# schematic.net
KiCad netlist of a schematic drawn in Altium Designer
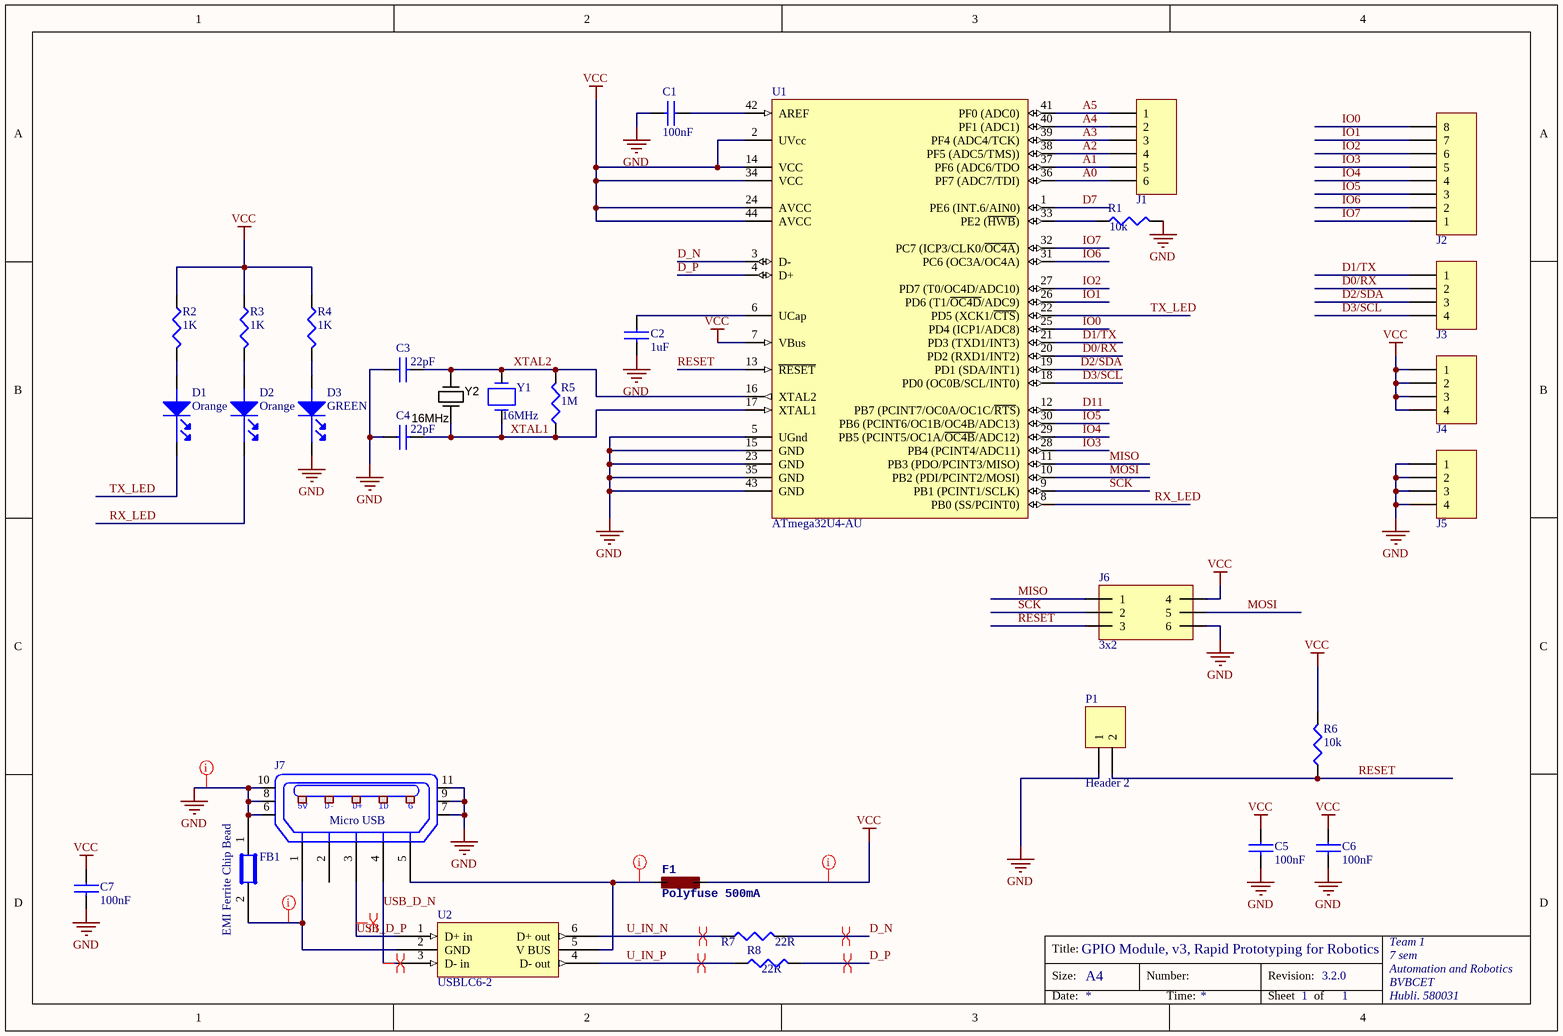
[diagram p0: schematic.SchDoc]

(export (version "E")
  (design (tool "Eeschema 10.0.6"))
  (components
    (comp (ref "C1")
      (value "100nF")
      (footprint "C0805")
      (description "CAP CER 16V 20% X5R 0805")
      (fields
        (field (name "MANUFACTURER") "TDK Corporation")
        (field (name "MANUFACTURER PART NUMBER") "C2012X5R1C106M/1.25")
      )
      (libsource (lib "GPIO_Module") (part "C2012X5R1C106M"))
    )
    (comp (ref "C2")
      (value "1uF")
      (footprint "C0805")
      (description "CAP CER 16V 20% X5R 0805")
      (fields
        (field (name "MANUFACTURER") "TDK Corporation")
        (field (name "MANUFACTURER PART NUMBER") "C2012X5R1C106M/1.25")
      )
      (libsource (lib "GPIO_Module") (part "C2012X5R1C106M"))
    )
    (comp (ref "C3")
      (value "22pF")
      (footprint "C0805")
      (description "CAP CER 22pF 50V 5% NP0 0805")
      (fields
        (field (name "MANUFACTURER") "Kemet")
        (field (name "MANUFACTURER PART NUMBER") "C0805C180J5GACTU")
        (field (name ".CREATOR") "MM")
        (field (name ".CHECKED PCB") "RF")
        (field (name ".CHECKED SCH") "RF")
      )
      (libsource (lib "GPIO_Module") (part "C0805C180J5GACTU"))
    )
    (comp (ref "C4")
      (value "22pF")
      (footprint "C0805")
      (description "CAP CER 22pF 50V 5% NP0 0805")
      (fields
        (field (name "MANUFACTURER") "Kemet")
        (field (name "MANUFACTURER PART NUMBER") "C0805C180J5GACTU")
        (field (name ".CREATOR") "MM")
        (field (name ".CHECKED PCB") "RF")
        (field (name ".CHECKED SCH") "RF")
      )
      (libsource (lib "GPIO_Module") (part "C0805C180J5GACTU"))
    )
    (comp (ref "C5")
      (value "100nF")
      (footprint "C0805")
      (description "CAP CER 0.1UF 50V 10% X7R 0805")
      (fields
        (field (name "MANUFACTURER") "TDK Corporation")
        (field (name "MANUFACTURER PART NUMBER") "C2012X7R1H104K085AA")
        (field (name ".CREATOR") "MM")
        (field (name ".CHECKED PCB") "RF")
        (field (name ".CHECKED SCH") "RF")
      )
      (libsource (lib "GPIO_Module") (part "C2012X7R1H104K085AA"))
    )
    (comp (ref "C6")
      (value "100nF")
      (footprint "C0805")
      (description "CAP CER 0.1UF 50V 10% X7R 0805")
      (fields
        (field (name "MANUFACTURER") "TDK Corporation")
        (field (name "MANUFACTURER PART NUMBER") "C2012X7R1H104K085AA")
        (field (name ".CREATOR") "MM")
        (field (name ".CHECKED PCB") "RF")
        (field (name ".CHECKED SCH") "RF")
      )
      (libsource (lib "GPIO_Module") (part "C2012X7R1H104K085AA"))
    )
    (comp (ref "C7")
      (value "100nF")
      (footprint "C0805")
      (description "CAP CER 0.1UF 50V 10% X7R 0805")
      (fields
        (field (name "MANUFACTURER") "TDK Corporation")
        (field (name "MANUFACTURER PART NUMBER") "C2012X7R1H104K085AA")
        (field (name ".CREATOR") "MM")
        (field (name ".CHECKED PCB") "RF")
        (field (name ".CHECKED SCH") "RF")
      )
      (libsource (lib "GPIO_Module") (part "C2012X7R1H104K085AA"))
    )
    (comp (ref "D1")
      (value "Orange")
      (footprint "LED_0603")
      (description "LED SMARTLED ORANGE 606NM 0603")
      (fields
        (field (name "MANUFACTURER") "OSRAM Opto Semiconductors Inc")
        (field (name "MANUFACTURER PART NUMBER") "LO L29K-H2K1-24-Z")
      )
      (libsource (lib "GPIO_Module") (part "LO L29K-H2K1-24-Z"))
    )
    (comp (ref "D2")
      (value "Orange")
      (footprint "LED_0603")
      (description "LED SMARTLED ORANGE 606NM 0603")
      (fields
        (field (name "MANUFACTURER") "OSRAM Opto Semiconductors Inc")
        (field (name "MANUFACTURER PART NUMBER") "LO L29K-H2K1-24-Z")
      )
      (libsource (lib "GPIO_Module") (part "LO L29K-H2K1-24-Z"))
    )
    (comp (ref "D3")
      (value "GREEN")
      (footprint "LED_0603")
      (description "LED SMARTLED ORANGE 606NM 0603")
      (fields
        (field (name "MANUFACTURER") "OSRAM Opto Semiconductors Inc")
        (field (name "MANUFACTURER PART NUMBER") "LO L29K-H2K1-24-Z")
      )
      (libsource (lib "GPIO_Module") (part "LO L29K-H2K1-24-Z"))
    )
    (comp (ref "F1")
      (value "Polyfuse 500mA")
      (footprint "L1812")
      (libsource (lib "GPIO_Module") (part "L-EUL1812"))
    )
    (comp (ref "FB1")
      (value "EMI Ferrite Chip Bead")
      (footprint "C0805")
      (description "Multilayer Ferrite Beads, Chip Beads in SMD 0805 package")
      (fields (field (name "MANUFACTURER") "Bourns") (field (name "MANUFACTURER PART NUMBER") "MH2029-300Y"))
      (libsource (lib "GPIO_Module") (part "MPZ2012S601AT000"))
    )
    (comp (ref "J1")
      (value "06p")
      (footprint "61300611821")
      (description "WR-PHD 2.54 mm Socket Header, 06p")
      (fields (field (name "PARTNUMBER") "61300611821") (field (name "PUBLISHER") "Wurth Elektronik"))
      (libsource (lib "ALTIUM-PHD_2_54_ANGLED_DUAL_SOCKET_HEADER_6130XX243121-rev16c") (part "61300611821"))
    )
    (comp (ref "J2")
      (value "08p")
      (footprint "61300811821")
      (description "WR-PHD 2.54 mm Socket Header, 08p")
      (fields (field (name "PARTNUMBER") "61300811821") (field (name "PUBLISHER") "Wurth Elektronik"))
      (libsource (lib "ALTIUM-PHD_2_54_ANGLED_DUAL_SOCKET_HEADER_6130XX243121-rev16c") (part "61300811821"))
    )
    (comp (ref "J3")
      (value "04p")
      (footprint "61300411821")
      (description "WR-PHD 2.54 mm Socket Header, 04p")
      (fields (field (name "PARTNUMBER") "61300411821") (field (name "PUBLISHER") "Wurth Elektronik"))
      (libsource (lib "ALTIUM-PHD_2_54_ANGLED_DUAL_SOCKET_HEADER_6130XX243121-rev16c") (part "61300411821"))
    )
    (comp (ref "J4")
      (value "04p")
      (footprint "61300411821")
      (description "WR-PHD 2.54 mm Socket Header, 04p")
      (fields (field (name "PARTNUMBER") "61300411821") (field (name "PUBLISHER") "Wurth Elektronik"))
      (libsource (lib "ALTIUM-PHD_2_54_ANGLED_DUAL_SOCKET_HEADER_6130XX243121-rev16c") (part "61300411821"))
    )
    (comp (ref "J5")
      (value "04p")
      (footprint "61300411821")
      (description "WR-PHD 2.54 mm Socket Header, 04p")
      (fields (field (name "PARTNUMBER") "61300411821") (field (name "PUBLISHER") "Wurth Elektronik"))
      (libsource (lib "ALTIUM-PHD_2_54_ANGLED_DUAL_SOCKET_HEADER_6130XX243121-rev16c") (part "61300411821"))
    )
    (comp (ref "J6")
      (value "3x2")
      (footprint "Headers:Male 3x2")
      (description "3x2 100mil Header")
      (libsource (lib "GPIO_Module") (part "3x2"))
    )
    (comp (ref "J7")
      (value "Micro USB")
      (footprint "10118193")
      (description "CONN USB MICRO B RECPT SMT R/A")
      (fields
        (field (name "MANUFACTURER") "FCI")
        (field (name "MANUFACTURER PART NUMBER") "10118193-0001LF")
        (field (name ".CREATOR") "MM")
        (field (name ".CHECKED PCB") "RF")
        (field (name ".CHECKED SCH") "MM")
      )
      (libsource (lib "GPIO_Module") (part "10118193-0001LF"))
    )
    (comp (ref "P1")
      (value "Header 2")
      (footprint "HDR1X2")
      (description "Header, 2-Pin")
      (fields (field (name "PUBLISHER") "Altium Limited"))
      (libsource (lib "Miscellaneous Connectors") (part "Header 2"))
    )
    (comp (ref "R1")
      (value "10k")
      (footprint "R0805")
      (description "RES SMD 10K OHM 1% 1/8W 0805")
      (fields
        (field (name "MANUFACTURER") "Yageo")
        (field (name "MANUFACTURER PART NUMBER") "RC0805FR-0710KL")
        (field (name ".CREATOR") "MM")
        (field (name ".CHECKED PCB") "RF")
        (field (name ".CHECKED SCH") "RF")
      )
      (libsource (lib "GPIO_Module") (part "RC0805FR-0710KL"))
    )
    (comp (ref "R2")
      (value "1K")
      (footprint "R0805")
      (description "RES SMD 1K OHM 1% 1/8W 0805")
      (fields
        (field (name "MANUFACTURER") "Yageo")
        (field (name "MANUFACTURER PART NUMBER") "RC0805FR-071KL")
        (field (name ".CREATOR") "MM")
        (field (name ".CHECKED PCB") "RF")
        (field (name ".CHECKED SCH") "RF")
      )
      (libsource (lib "GPIO_Module") (part "RC0805FR-071KL"))
    )
    (comp (ref "R3")
      (value "1K")
      (footprint "R0805")
      (description "RES SMD 1K OHM 1% 1/8W 0805")
      (fields
        (field (name "MANUFACTURER") "Yageo")
        (field (name "MANUFACTURER PART NUMBER") "RC0805FR-071KL")
        (field (name ".CREATOR") "MM")
        (field (name ".CHECKED PCB") "RF")
        (field (name ".CHECKED SCH") "RF")
      )
      (libsource (lib "GPIO_Module") (part "RC0805FR-071KL"))
    )
    (comp (ref "R4")
      (value "1K")
      (footprint "R0805")
      (description "RES SMD 1K OHM 1% 1/8W 0805")
      (fields
        (field (name "MANUFACTURER") "Yageo")
        (field (name "MANUFACTURER PART NUMBER") "RC0805FR-071KL")
        (field (name ".CREATOR") "MM")
        (field (name ".CHECKED PCB") "RF")
        (field (name ".CHECKED SCH") "RF")
      )
      (libsource (lib "GPIO_Module") (part "RC0805FR-071KL"))
    )
    (comp (ref "R5")
      (value "1M")
      (footprint "R0805")
      (description "RES SMD 1M OHM 1% 1/8W 0805")
      (fields
        (field (name "MANUFACTURER") "Yageo")
        (field (name "MANUFACTURER PART NUMBER") "RC0805FR-071ML")
        (field (name ".CREATOR") "MM")
        (field (name ".CHECKED PCB") "RF")
        (field (name ".CHECKED SCH") "RF")
      )
      (libsource (lib "GPIO_Module") (part "RC0805FR-071ML"))
    )
    (comp (ref "R6")
      (value "10k")
      (footprint "R0805")
      (description "RES SMD 10K OHM 1% 1/8W 0805")
      (fields
        (field (name "MANUFACTURER") "Yageo")
        (field (name "MANUFACTURER PART NUMBER") "RC0805FR-0710KL")
        (field (name ".CREATOR") "MM")
        (field (name ".CHECKED PCB") "RF")
        (field (name ".CHECKED SCH") "RF")
      )
      (libsource (lib "GPIO_Module") (part "RC0805FR-0710KL"))
    )
    (comp (ref "R7")
      (value "22R")
      (footprint "R0805")
      (description "RES SMD 22 OHM 1% 1/8W 0805")
      (fields
        (field (name "MANUFACTURER") "Yageo")
        (field (name "MANUFACTURER PART NUMBER") "RC0805FR-0722RL")
        (field (name ".CREATOR") "MM")
        (field (name ".CHECKED PCB") "RF")
        (field (name ".CHECKED SCH") "RF")
      )
      (libsource (lib "GPIO_Module") (part "RC0805FR-0722RL"))
    )
    (comp (ref "R8")
      (value "22R")
      (footprint "R0805")
      (description "RES SMD 22 OHM 1% 1/8W 0805")
      (fields
        (field (name "MANUFACTURER") "Yageo")
        (field (name "MANUFACTURER PART NUMBER") "RC0805FR-0722RL")
        (field (name ".CREATOR") "MM")
        (field (name ".CHECKED PCB") "RF")
        (field (name ".CHECKED SCH") "RF")
      )
      (libsource (lib "GPIO_Module") (part "RC0805FR-0722RL"))
    )
    (comp (ref "U1")
      (value "ATmega32U4-AU")
      (footprint "44ML_M")
      (fields (field (name "PUBLISHER") "Altium Limited"))
      (libsource (lib "GPIO_Module") (part "ATmega32U4-AU"))
    )
    (comp (ref "U2")
      (value "USBLC6-2")
      (footprint "TSOT23-6")
      (libsource (lib "GPIO_Module") (part "USBLC6-2"))
    )
    (comp (ref "Y1")
      (value "16MHz")
      (footprint "ABM7_v1_1_BIG")
      (description "CRYSTAL 16MHZ 18PF SMD")
      (fields
        (field (name "MANUFACTURER") "Abracon LLC")
        (field (name "MANUFACTURER PART NUMBER") "ABM7-16.000MHZ-D2Y-T")
        (field (name ".CREATOR") "MM")
        (field (name ".CHECKED PCB") "RF")
        (field (name ".CHECKED SCH") "RF")
      )
      (libsource (lib "GPIO_Module") (part "ABM7-16.000MHZ-D2Y-T"))
    )
    (comp (ref "Y2")
      (value "16MHz")
      (footprint "CRYSTAL_HC49-US-SM")
      (description "Resonator Ceramic 6.00 MHz 30ppm")
      (libsource (lib "PBL - Resonators") (part "Crystal_6MHz_HC49/US"))
    )
  )
  (nets
    (net (code "1") (name "/A0") (class "Default")
      (node (ref "J1") (pin "6") (pinfunction "6_6") (pintype "passive"))
      (node (ref "U1") (pin "36") (pinfunction "PF7_(ADC7/TDI)_36") (pintype "bidirectional"))
    )
    (net (code "2") (name "/A1") (class "Default")
      (node (ref "J1") (pin "5") (pinfunction "5_5") (pintype "passive"))
      (node (ref "U1") (pin "37") (pinfunction "PF6_(ADC6/TDO_37") (pintype "bidirectional"))
    )
    (net (code "3") (name "/A2") (class "Default")
      (node (ref "J1") (pin "4") (pinfunction "4_4") (pintype "passive"))
      (node (ref "U1") (pin "38") (pinfunction "PF5_(ADC5/TMS))_38") (pintype "bidirectional"))
    )
    (net (code "4") (name "/A3") (class "Default")
      (node (ref "J1") (pin "3") (pinfunction "3_3") (pintype "passive"))
      (node (ref "U1") (pin "39") (pinfunction "PF4_(ADC4/TCK)_39") (pintype "bidirectional"))
    )
    (net (code "5") (name "/A4") (class "Default")
      (node (ref "J1") (pin "2") (pinfunction "2_2") (pintype "passive"))
      (node (ref "U1") (pin "40") (pinfunction "PF1_(ADC1)_40") (pintype "bidirectional"))
    )
    (net (code "6") (name "/A5") (class "Default")
      (node (ref "J1") (pin "1") (pinfunction "1_1") (pintype "passive"))
      (node (ref "U1") (pin "41") (pinfunction "PF0_(ADC0)_41") (pintype "bidirectional"))
    )
    (net (code "7") (name "/D0{slash}RX") (class "Default")
      (node (ref "J3") (pin "2") (pinfunction "2_2") (pintype "passive"))
      (node (ref "U1") (pin "20") (pinfunction "PD2_(RXD1/INT2)_20") (pintype "bidirectional"))
    )
    (net (code "8") (name "/D1{slash}TX") (class "Default")
      (node (ref "J3") (pin "1") (pinfunction "1_1") (pintype "passive"))
      (node (ref "U1") (pin "21") (pinfunction "PD3_(TXD1/INT3)_21") (pintype "bidirectional"))
    )
    (net (code "9") (name "/D2{slash}SDA") (class "Default")
      (node (ref "J3") (pin "3") (pinfunction "3_3") (pintype "passive"))
      (node (ref "U1") (pin "19") (pinfunction "PD1_(SDA/INT1)_19") (pintype "bidirectional"))
    )
    (net (code "10") (name "/D3{slash}SCL") (class "Default")
      (node (ref "J3") (pin "4") (pinfunction "4_4") (pintype "passive"))
      (node (ref "U1") (pin "18") (pinfunction "PD0_(OC0B/SCL/INT0)_18") (pintype "bidirectional"))
    )
    (net (code "11") (name "/D7") (class "Default")
      (node (ref "U1") (pin "1") (pinfunction "PE6_(INT.6/AIN0)_1") (pintype "bidirectional"))
    )
    (net (code "12") (name "/D11") (class "Default")
      (node (ref "U1") (pin "12") (pinfunction "PB7_(PCINT7/OC0A/OC1C/~{RTS})_12") (pintype "bidirectional"))
    )
    (net (code "13") (name "/D_N") (class "Default")
      (node (ref "R7") (pin "2") (pinfunction "2_2") (pintype "passive"))
      (node (ref "U1") (pin "3") (pinfunction "D-_3") (pintype "bidirectional"))
    )
    (net (code "14") (name "/D_P") (class "Default")
      (node (ref "R8") (pin "2") (pinfunction "2_2") (pintype "passive"))
      (node (ref "U1") (pin "4") (pinfunction "D+_4") (pintype "bidirectional"))
    )
    (net (code "15") (name "/IO0") (class "Default")
      (node (ref "J2") (pin "8") (pinfunction "8_8") (pintype "passive"))
      (node (ref "U1") (pin "25") (pinfunction "PD4_(ICP1/ADC8)_25") (pintype "bidirectional"))
    )
    (net (code "16") (name "/IO1") (class "Default")
      (node (ref "J2") (pin "7") (pinfunction "7_7") (pintype "passive"))
      (node (ref "U1") (pin "26") (pinfunction "PD6_(T1/~{OC4D}/ADC9)_26") (pintype "bidirectional"))
    )
    (net (code "17") (name "/IO2") (class "Default")
      (node (ref "J2") (pin "6") (pinfunction "6_6") (pintype "passive"))
      (node (ref "U1") (pin "27") (pinfunction "PD7_(T0/OC4D/ADC10)_27") (pintype "bidirectional"))
    )
    (net (code "18") (name "/IO3") (class "Default")
      (node (ref "J2") (pin "5") (pinfunction "5_5") (pintype "passive"))
      (node (ref "U1") (pin "28") (pinfunction "PB4_(PCINT4/ADC11)_28") (pintype "bidirectional"))
    )
    (net (code "19") (name "/IO4") (class "Default")
      (node (ref "J2") (pin "4") (pinfunction "4_4") (pintype "passive"))
      (node (ref "U1") (pin "29") (pinfunction "PB5_(PCINT5/OC1A/~{OC4B}/ADC12)_29") (pintype "bidirectional"))
    )
    (net (code "20") (name "/IO5") (class "Default")
      (node (ref "J2") (pin "3") (pinfunction "3_3") (pintype "passive"))
      (node (ref "U1") (pin "30") (pinfunction "PB6_(PCINT6/OC1B/OC4B/ADC13)_30") (pintype "bidirectional"))
    )
    (net (code "21") (name "/IO6") (class "Default")
      (node (ref "J2") (pin "2") (pinfunction "2_2") (pintype "passive"))
      (node (ref "U1") (pin "31") (pinfunction "PC6_(OC3A/OC4A)_31") (pintype "bidirectional"))
    )
    (net (code "22") (name "/IO7") (class "Default")
      (node (ref "J2") (pin "1") (pinfunction "1_1") (pintype "passive"))
      (node (ref "U1") (pin "32") (pinfunction "PC7_(ICP3/CLK0/~{OC4A})_32") (pintype "bidirectional"))
    )
    (net (code "23") (name "/MISO") (class "Default")
      (node (ref "J6") (pin "1") (pinfunction "1_1") (pintype "passive"))
      (node (ref "U1") (pin "11") (pinfunction "PB3_(PDO/PCINT3/MISO)_11") (pintype "bidirectional"))
    )
    (net (code "24") (name "/MOSI") (class "Default")
      (node (ref "J6") (pin "5") (pinfunction "5_5") (pintype "passive"))
      (node (ref "U1") (pin "10") (pinfunction "PB2_(PDI/PCINT2/MOSI)_10") (pintype "bidirectional"))
    )
    (net (code "25") (name "/RESET") (class "Default")
      (node (ref "J6") (pin "3") (pinfunction "3_3") (pintype "passive"))
      (node (ref "P1") (pin "2") (pinfunction "2_2") (pintype "passive"))
      (node (ref "R6") (pin "1") (pinfunction "1_1") (pintype "passive"))
      (node (ref "U1") (pin "13") (pinfunction "~{RESET}_13") (pintype "input"))
    )
    (net (code "26") (name "/RX_LED") (class "Default")
      (node (ref "D2") (pin "1") (pinfunction "cathode_1") (pintype "passive"))
      (node (ref "U1") (pin "8") (pinfunction "PB0_(SS/PCINT0)_8") (pintype "bidirectional"))
    )
    (net (code "27") (name "/SCK") (class "Default")
      (node (ref "J6") (pin "2") (pinfunction "2_2") (pintype "passive"))
      (node (ref "U1") (pin "9") (pinfunction "PB1_(PCINT1/SCLK)_9") (pintype "bidirectional"))
    )
    (net (code "28") (name "/TX_LED") (class "Default")
      (node (ref "D1") (pin "1") (pinfunction "cathode_1") (pintype "passive"))
      (node (ref "U1") (pin "22") (pinfunction "PD5_(XCK1/~{CTS})_22") (pintype "bidirectional"))
    )
    (net (code "29") (name "/USB_D_N") (class "Default")
      (node (ref "J7") (pin "4") (pinfunction "P4_4") (pintype "passive"))
      (node (ref "U2") (pin "3") (pinfunction "D-_in_3") (pintype "input"))
    )
    (net (code "30") (name "/USB_D_P") (class "Default")
      (node (ref "J7") (pin "3") (pinfunction "P3_3") (pintype "passive"))
      (node (ref "U2") (pin "1") (pinfunction "D+_in_1") (pintype "input"))
    )
    (net (code "31") (name "/U_IN_N") (class "Default")
      (node (ref "R7") (pin "1") (pinfunction "1_1") (pintype "passive"))
      (node (ref "U2") (pin "6") (pinfunction "D+_out_6") (pintype "output"))
    )
    (net (code "32") (name "/U_IN_P") (class "Default")
      (node (ref "R8") (pin "1") (pinfunction "1_1") (pintype "passive"))
      (node (ref "U2") (pin "4") (pinfunction "D-_out_4") (pintype "output"))
    )
    (net (code "33") (name "/XTAL1") (class "Default")
      (node (ref "C4") (pin "2") (pinfunction "2_2") (pintype "passive"))
      (node (ref "R5") (pin "1") (pinfunction "1_1") (pintype "passive"))
      (node (ref "U1") (pin "17") (pinfunction "XTAL1_17") (pintype "input"))
      (node (ref "Y1") (pin "1") (pinfunction "1_1") (pintype "passive"))
      (node (ref "Y2") (pin "1") (pinfunction "IN_1") (pintype "passive"))
    )
    (net (code "34") (name "/XTAL2") (class "Default")
      (node (ref "C3") (pin "2") (pinfunction "2_2") (pintype "passive"))
      (node (ref "R5") (pin "2") (pinfunction "2_2") (pintype "passive"))
      (node (ref "U1") (pin "16") (pinfunction "XTAL2_16") (pintype "output"))
      (node (ref "Y1") (pin "2") (pinfunction "2_2") (pintype "passive"))
      (node (ref "Y2") (pin "2") (pinfunction "OUT_2") (pintype "passive"))
    )
    (net (code "35") (name "GND") (class "Default")
      (node (ref "C1") (pin "2") (pinfunction "2_2") (pintype "passive"))
      (node (ref "C2") (pin "2") (pinfunction "2_2") (pintype "passive"))
      (node (ref "C3") (pin "1") (pinfunction "1_1") (pintype "passive"))
      (node (ref "C4") (pin "1") (pinfunction "1_1") (pintype "passive"))
      (node (ref "C5") (pin "2") (pinfunction "2_2") (pintype "passive"))
      (node (ref "C6") (pin "2") (pinfunction "2_2") (pintype "passive"))
      (node (ref "C7") (pin "2") (pinfunction "2_2") (pintype "passive"))
      (node (ref "D3") (pin "1") (pinfunction "cathode_1") (pintype "passive"))
      (node (ref "FB1") (pin "1") (pinfunction "1_1") (pintype "passive"))
      (node (ref "J5") (pin "1") (pinfunction "1_1") (pintype "passive"))
      (node (ref "J5") (pin "2") (pinfunction "2_2") (pintype "passive"))
      (node (ref "J5") (pin "3") (pinfunction "3_3") (pintype "passive"))
      (node (ref "J5") (pin "4") (pinfunction "4_4") (pintype "passive"))
      (node (ref "J6") (pin "6") (pinfunction "6_6") (pintype "passive"))
      (node (ref "J7") (pin "10") (pinfunction "10_10") (pintype "passive"))
      (node (ref "J7") (pin "11") (pinfunction "11_11") (pintype "passive"))
      (node (ref "J7") (pin "6") (pinfunction "6_6") (pintype "passive"))
      (node (ref "J7") (pin "7") (pinfunction "7_7") (pintype "passive"))
      (node (ref "J7") (pin "8") (pinfunction "8_8") (pintype "passive"))
      (node (ref "J7") (pin "9") (pinfunction "9_9") (pintype "passive"))
      (node (ref "P1") (pin "1") (pinfunction "1_1") (pintype "passive"))
      (node (ref "R1") (pin "2") (pinfunction "2_2") (pintype "passive"))
      (node (ref "U1") (pin "15") (pinfunction "GND_15") (pintype "power_in"))
      (node (ref "U1") (pin "23") (pinfunction "GND_23") (pintype "power_in"))
      (node (ref "U1") (pin "35") (pinfunction "GND_35") (pintype "power_in"))
      (node (ref "U1") (pin "43") (pinfunction "GND_43") (pintype "power_in"))
      (node (ref "U1") (pin "5") (pinfunction "UGnd_5") (pintype "power_in"))
    )
    (net (code "36") (name "Net-(D1-ANODE)") (class "Default")
      (node (ref "D1") (pin "2") (pinfunction "ANODE_2") (pintype "passive"))
      (node (ref "R2") (pin "2") (pinfunction "2_2") (pintype "passive"))
    )
    (net (code "37") (name "Net-(D2-ANODE)") (class "Default")
      (node (ref "D2") (pin "2") (pinfunction "ANODE_2") (pintype "passive"))
      (node (ref "R3") (pin "2") (pinfunction "2_2") (pintype "passive"))
    )
    (net (code "38") (name "Net-(D3-ANODE)") (class "Default")
      (node (ref "D3") (pin "2") (pinfunction "ANODE_2") (pintype "passive"))
      (node (ref "R4") (pin "2") (pinfunction "2_2") (pintype "passive"))
    )
    (net (code "39") (name "Net-(J7-P1)") (class "Default")
      (node (ref "FB1") (pin "2") (pinfunction "2_2") (pintype "passive"))
      (node (ref "J7") (pin "1") (pinfunction "P1_1") (pintype "passive"))
      (node (ref "U2") (pin "2") (pinfunction "GND_2") (pintype "power_in"))
    )
    (net (code "40") (name "Net-(J7-P5)") (class "Default")
      (node (ref "F1") (pin "1") (pinfunction "1_1") (pintype "passive"))
      (node (ref "J7") (pin "5") (pinfunction "P5_5") (pintype "passive"))
      (node (ref "U2") (pin "5") (pinfunction "V_BUS_5") (pintype "power_in"))
    )
    (net (code "41") (name "Net-(U1-AREF)") (class "Default")
      (node (ref "C1") (pin "1") (pinfunction "1_1") (pintype "passive"))
      (node (ref "U1") (pin "42") (pinfunction "AREF_42") (pintype "input"))
    )
    (net (code "42") (name "Net-(U1-PE2_(~{HWB}))") (class "Default")
      (node (ref "R1") (pin "1") (pinfunction "1_1") (pintype "passive"))
      (node (ref "U1") (pin "33") (pinfunction "PE2_(~{HWB})_33") (pintype "bidirectional"))
    )
    (net (code "43") (name "Net-(U1-UCap)") (class "Default")
      (node (ref "C2") (pin "1") (pinfunction "1_1") (pintype "passive"))
      (node (ref "U1") (pin "6") (pinfunction "UCap_6") (pintype "passive"))
    )
    (net (code "44") (name "VCC") (class "Default")
      (node (ref "C5") (pin "1") (pinfunction "1_1") (pintype "passive"))
      (node (ref "C6") (pin "1") (pinfunction "1_1") (pintype "passive"))
      (node (ref "C7") (pin "1") (pinfunction "1_1") (pintype "passive"))
      (node (ref "F1") (pin "2") (pinfunction "2_2") (pintype "passive"))
      (node (ref "J4") (pin "1") (pinfunction "1_1") (pintype "passive"))
      (node (ref "J4") (pin "2") (pinfunction "2_2") (pintype "passive"))
      (node (ref "J4") (pin "3") (pinfunction "3_3") (pintype "passive"))
      (node (ref "J4") (pin "4") (pinfunction "4_4") (pintype "passive"))
      (node (ref "J6") (pin "4") (pinfunction "4_4") (pintype "passive"))
      (node (ref "R2") (pin "1") (pinfunction "1_1") (pintype "passive"))
      (node (ref "R3") (pin "1") (pinfunction "1_1") (pintype "passive"))
      (node (ref "R4") (pin "1") (pinfunction "1_1") (pintype "passive"))
      (node (ref "R6") (pin "2") (pinfunction "2_2") (pintype "passive"))
      (node (ref "U1") (pin "14") (pinfunction "VCC_14") (pintype "power_in"))
      (node (ref "U1") (pin "2") (pinfunction "UVcc_2") (pintype "power_in"))
      (node (ref "U1") (pin "24") (pinfunction "AVCC_24") (pintype "power_in"))
      (node (ref "U1") (pin "34") (pinfunction "VCC_34") (pintype "power_in"))
      (node (ref "U1") (pin "44") (pinfunction "AVCC_44") (pintype "power_in"))
      (node (ref "U1") (pin "7") (pinfunction "VBus_7") (pintype "input"))
    )
    (net (code "45") (name "unconnected-(J7-P2-Pad2)") (class "Default")
      (node (ref "J7") (pin "2") (pinfunction "P2_2") (pintype "passive"))
    )
  )
)
